# power.net
KiCad netlist of a schematic drawn in Altium Designer
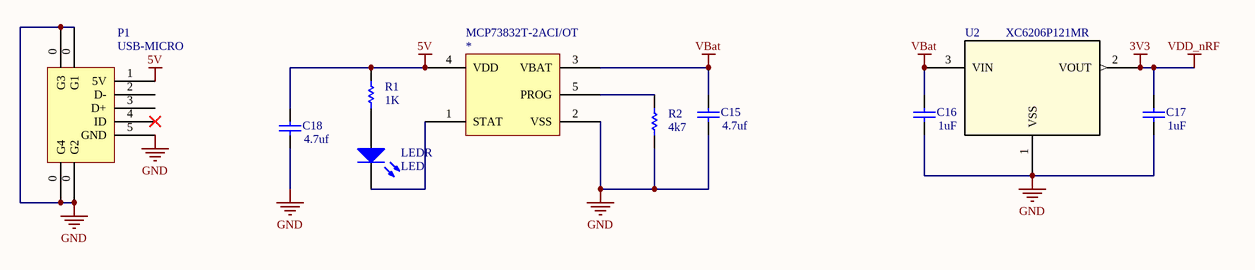
[diagram p0: power.SchDoc]

(export (version "E")
  (design (tool "Eeschema 10.0.6"))
  (components
    (comp (ref "*")
      (value "MCP73832T-2ACI/OT")
      (footprint "SOT-23-OT5_M")
      (libsource (lib "Mylibrary") (part "MCP73832T-2ACI/OT"))
    )
    (comp (ref "C15")
      (value "4.7uf")
      (footprint "C0603")
      (description "Capacitor (Semiconductor SIM Model)")
      (fields (field (name "Comment") "Cap Semi") (field (name "PUBLISHER") "Altium Limited"))
      (libsource (lib "Mylibrary") (part "Cap Semi"))
    )
    (comp (ref "C16")
      (value "1uF")
      (footprint "C0603")
      (description "Capacitor (Semiconductor SIM Model)")
      (fields (field (name "Comment") "Cap Semi") (field (name "PUBLISHER") "Altium Limited"))
      (libsource (lib "Mylibrary") (part "Cap Semi"))
    )
    (comp (ref "C17")
      (value "1uF")
      (footprint "C0603")
      (description "Capacitor (Semiconductor SIM Model)")
      (fields (field (name "Comment") "Cap Semi") (field (name "PUBLISHER") "Altium Limited"))
      (libsource (lib "Mylibrary") (part "Cap Semi"))
    )
    (comp (ref "C18")
      (value "4.7uf")
      (footprint "C0603")
      (description "Capacitor (Semiconductor SIM Model)")
      (fields (field (name "Comment") "Cap Semi") (field (name "PUBLISHER") "Altium Limited"))
      (libsource (lib "Mylibrary") (part "Cap Semi"))
    )
    (comp (ref "LEDR")
      (value "LED")
      (footprint "0603")
      (description "Typical INFRARED GaAs LED")
      (fields (field (name "PUBLISHER") "Altium Limited"))
      (libsource (lib "Mylibrary") (part "LED"))
    )
    (comp (ref "P1")
      (value "USB-MICRO")
      (footprint "USB-MICRO")
      (libsource (lib "Mylibrary") (part "USB-MICRO"))
    )
    (comp (ref "R1")
      (value "1K")
      (footprint "R0603-M")
      (description "Resistor")
      (fields (field (name "Comment") "Resistors SMD"))
      (libsource (lib "Mylibrary") (part "Resistors SMD"))
    )
    (comp (ref "R2")
      (value "4k7")
      (footprint "R0603-M")
      (description "Resistor")
      (fields (field (name "Comment") "Resistors SMD"))
      (libsource (lib "Mylibrary") (part "Resistors SMD"))
    )
    (comp (ref "U2")
      (value "XC6206P121MR")
      (footprint "SOT-23")
      (description "Imported")
      (libsource (lib "Mylibrary") (part "XC6206P121MR"))
    )
  )
  (nets
    (net (code "1") (name "3V3") (class "Default")
      (node (ref "C17") (pin "2") (pinfunction "2_2") (pintype "passive"))
      (node (ref "U2") (pin "2") (pinfunction "VOUT_2") (pintype "output"))
    )
    (net (code "2") (name "5V") (class "Default")
      (node (ref "*") (pin "4") (pinfunction "VDD_4") (pintype "passive"))
      (node (ref "C18") (pin "2") (pinfunction "2_2") (pintype "passive"))
      (node (ref "P1") (pin "1") (pinfunction "5V_1") (pintype "passive"))
      (node (ref "R1") (pin "2") (pinfunction "2_2") (pintype "passive"))
    )
    (net (code "3") (name "GND") (class "Default")
      (node (ref "*") (pin "2") (pinfunction "VSS_2") (pintype "passive"))
      (node (ref "C15") (pin "1") (pinfunction "1_1") (pintype "passive"))
      (node (ref "C16") (pin "1") (pinfunction "1_1") (pintype "passive"))
      (node (ref "C17") (pin "1") (pinfunction "1_1") (pintype "passive"))
      (node (ref "C18") (pin "1") (pinfunction "1_1") (pintype "passive"))
      (node (ref "P1") (pin "0") (pinfunction "G3_0") (pintype "power_in"))
      (node (ref "P1") (pin "5") (pinfunction "GND_5") (pintype "passive"))
      (node (ref "R2") (pin "1") (pinfunction "1_1") (pintype "passive"))
      (node (ref "U2") (pin "1") (pinfunction "VSS_1") (pintype "passive"))
    )
    (net (code "4") (name "Net-(*-PROG)") (class "Default")
      (node (ref "*") (pin "5") (pinfunction "PROG_5") (pintype "passive"))
      (node (ref "R2") (pin "2") (pinfunction "2_2") (pintype "passive"))
    )
    (net (code "5") (name "Net-(*-STAT)") (class "Default")
      (node (ref "*") (pin "1") (pinfunction "STAT_1") (pintype "passive"))
      (node (ref "LEDR") (pin "2") (pinfunction "K_2") (pintype "passive"))
    )
    (net (code "6") (name "Net-(LEDR-A)") (class "Default")
      (node (ref "LEDR") (pin "1") (pinfunction "A_1") (pintype "passive"))
      (node (ref "R1") (pin "1") (pinfunction "1_1") (pintype "passive"))
    )
    (net (code "7") (name "VBat") (class "Default")
      (node (ref "*") (pin "3") (pinfunction "VBAT_3") (pintype "passive"))
      (node (ref "C15") (pin "2") (pinfunction "2_2") (pintype "passive"))
      (node (ref "C16") (pin "2") (pinfunction "2_2") (pintype "passive"))
      (node (ref "U2") (pin "3") (pinfunction "VIN_3") (pintype "power_in"))
    )
    (net (code "8") (name "unconnected-(P1-D+-Pad3)") (class "Default")
      (node (ref "P1") (pin "3") (pinfunction "D+_3") (pintype "passive"))
    )
    (net (code "9") (name "unconnected-(P1-D--Pad2)") (class "Default")
      (node (ref "P1") (pin "2") (pinfunction "D-_2") (pintype "passive"))
    )
    (net (code "10") (name "unconnected-(P1-ID-Pad4)") (class "Default")
      (node (ref "P1") (pin "4") (pinfunction "ID_4") (pintype "passive+no_connect"))
    )
  )
)
